# ingress.net
KiCad netlist of a schematic drawn in Altium Designer
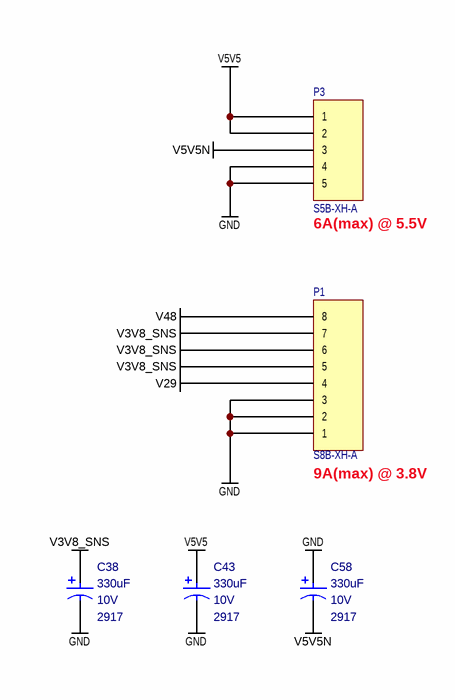
[diagram p0: ingress.SchDoc]

(export (version "E")
  (design (tool "Eeschema 10.0.6"))
  (components
    (comp (ref "C38")
      (value "330uF")
      (footprint "CAPPM730X435X310L135X240N")
      (description "Tantalum Capacitor 330uF ±10% 10V 2917")
      (fields
        (field (name "MANUFACTURER") "AVX")
        (field (name "TOLERANCE") "±10%")
        (field (name "PACKAGE") "2917")
        (field (name "VOLTAGE") "10V")
      )
      (libsource (lib "avx") (part "CAP_POL"))
    )
    (comp (ref "C43")
      (value "330uF")
      (footprint "CAPPM730X435X310L135X240N")
      (description "Tantalum Capacitor 330uF ±10% 10V 2917")
      (fields
        (field (name "MANUFACTURER") "AVX")
        (field (name "TOLERANCE") "±10%")
        (field (name "PACKAGE") "2917")
        (field (name "VOLTAGE") "10V")
      )
      (libsource (lib "avx") (part "CAP_POL"))
    )
    (comp (ref "C58")
      (value "330uF")
      (footprint "CAPPM730X435X310L135X240N")
      (description "Tantalum Capacitor 330uF ±10% 10V 2917")
      (fields
        (field (name "MANUFACTURER") "AVX")
        (field (name "TOLERANCE") "±10%")
        (field (name "PACKAGE") "2917")
        (field (name "VOLTAGE") "10V")
      )
      (libsource (lib "avx") (part "CAP_POL"))
    )
    (comp (ref "P1")
      (value "S8B-XH-A")
      (footprint "jst:S8B-XH-A")
      (description "2.5mm pitch right angle 8-position")
      (fields (field (name "MANUFACTURER") "JST"))
      (libsource (lib "jst") (part "S8B-XH-A"))
    )
    (comp (ref "P3")
      (value "S5B-XH-A")
      (footprint "jst:S5B-XH-A")
      (description "2.5mm pitch right angle 5-position")
      (fields (field (name "MANUFACTURER") "JST"))
      (libsource (lib "jst") (part "S5B-XH-A"))
    )
  )
  (nets
    (net (code "1") (name "GND") (class "Default")
      (node (ref "C38") (pin "2") (pinfunction "2_2") (pintype "passive"))
      (node (ref "C43") (pin "2") (pinfunction "2_2") (pintype "passive"))
      (node (ref "C58") (pin "1") (pinfunction "1_1") (pintype "passive"))
      (node (ref "P1") (pin "1") (pinfunction "1_1") (pintype "passive"))
      (node (ref "P1") (pin "2") (pinfunction "2_2") (pintype "passive"))
      (node (ref "P1") (pin "3") (pinfunction "3_3") (pintype "passive"))
      (node (ref "P3") (pin "4") (pinfunction "4_4") (pintype "passive"))
      (node (ref "P3") (pin "5") (pinfunction "5_5") (pintype "passive"))
    )
    (net (code "2") (name "V3V8_SNS") (class "Default")
      (node (ref "C38") (pin "1") (pinfunction "1_1") (pintype "passive"))
      (node (ref "P1") (pin "5") (pinfunction "5_5") (pintype "passive"))
      (node (ref "P1") (pin "6") (pinfunction "6_6") (pintype "passive"))
      (node (ref "P1") (pin "7") (pinfunction "7_7") (pintype "passive"))
    )
    (net (code "3") (name "V5V5") (class "Default")
      (node (ref "C43") (pin "1") (pinfunction "1_1") (pintype "passive"))
      (node (ref "P3") (pin "1") (pinfunction "1_1") (pintype "passive"))
      (node (ref "P3") (pin "2") (pinfunction "2_2") (pintype "passive"))
    )
    (net (code "4") (name "V5V5N") (class "Default")
      (node (ref "C58") (pin "2") (pinfunction "2_2") (pintype "passive"))
      (node (ref "P3") (pin "3") (pinfunction "3_3") (pintype "passive"))
    )
    (net (code "5") (name "V29") (class "Default")
      (node (ref "P1") (pin "4") (pinfunction "4_4") (pintype "passive"))
    )
    (net (code "6") (name "V48") (class "Default")
      (node (ref "P1") (pin "8") (pinfunction "8_8") (pintype "passive"))
    )
  )
)
